# PCB-BI8-SE-C330.net
KiCad netlist of a schematic drawn in EAGLE
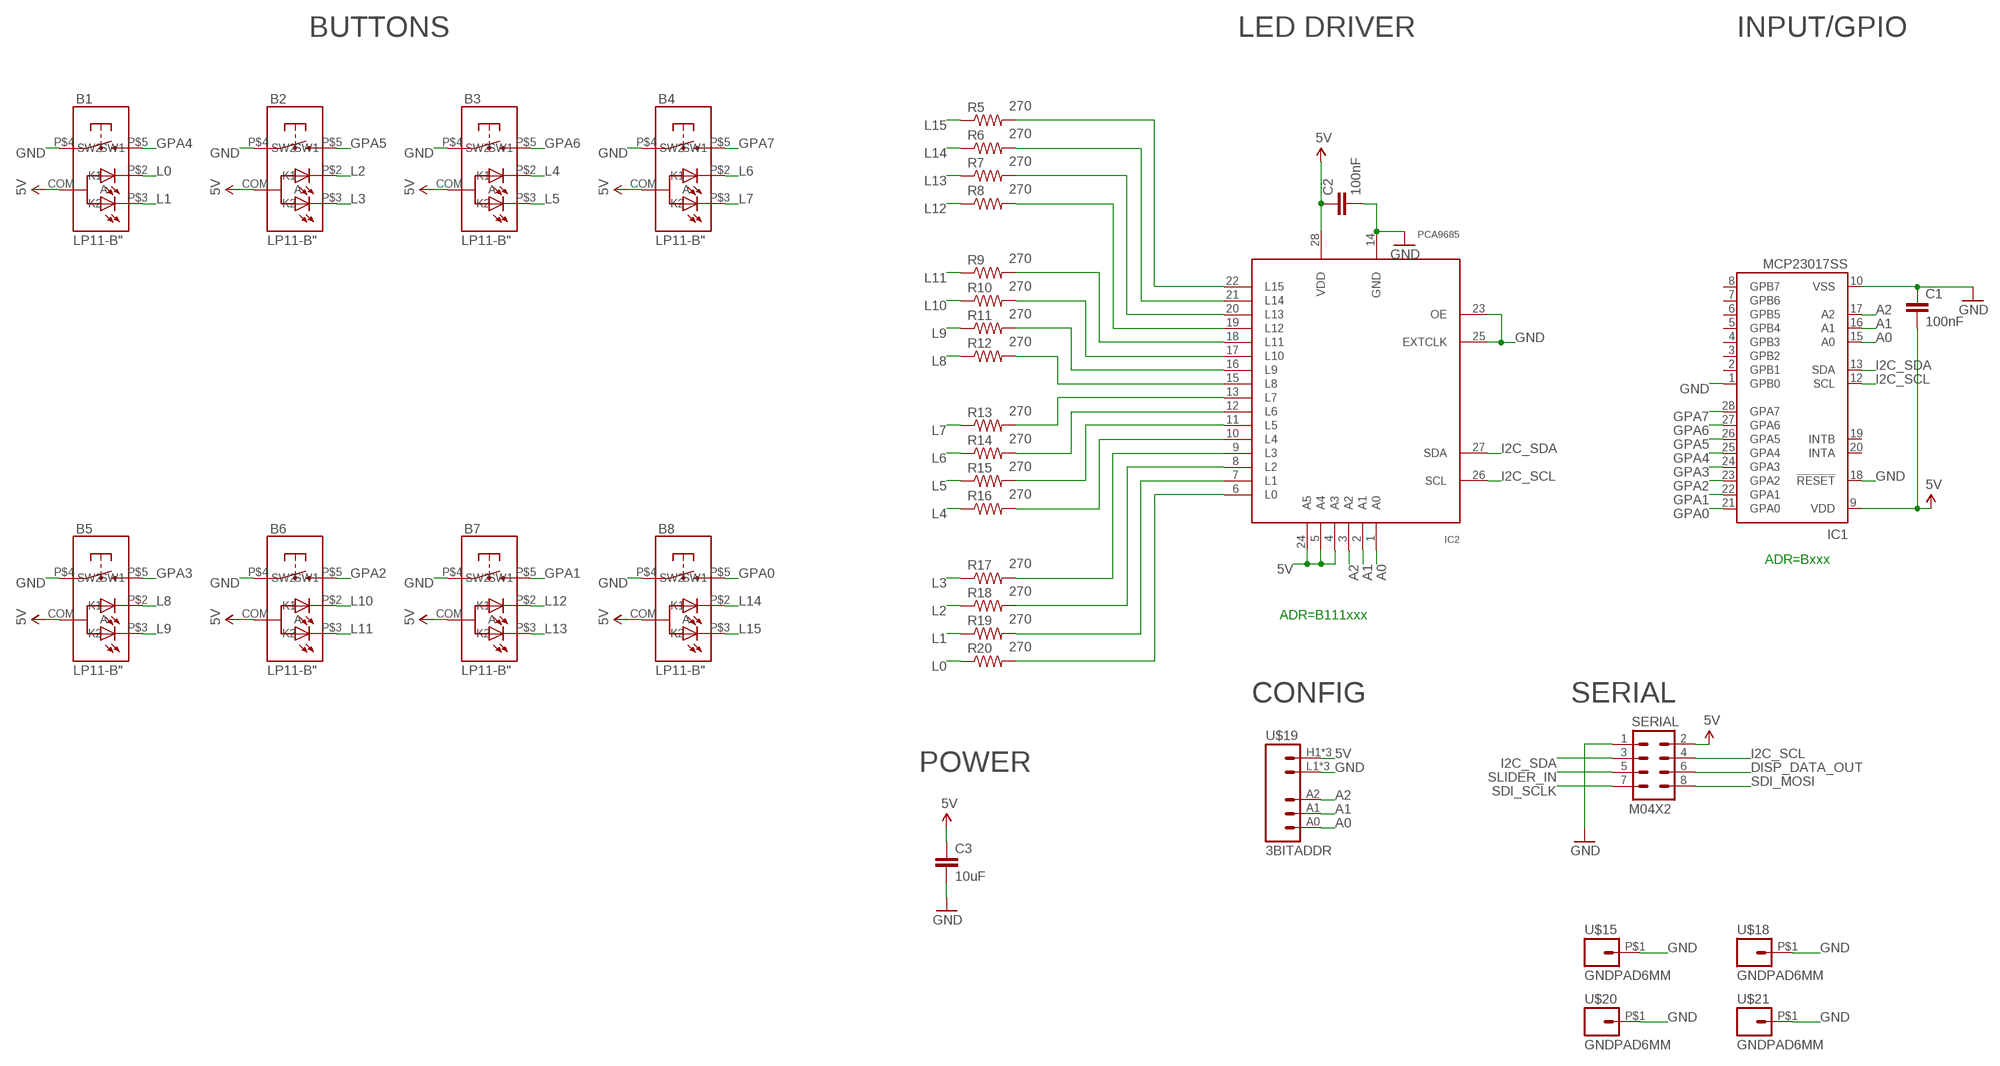
[diagram p0: schematic, sheet 1]

(export (version "E")
  (design (tool "Eeschema 10.0.6"))
  (components
    (comp (ref "B1")
      (value "LP11-B\"")
      (footprint "eagle-import:LP11")
      (libsource (lib "eagle-import") (part "LP11-B{dblquote}"))
    )
    (comp (ref "B2")
      (value "LP11-B\"")
      (footprint "eagle-import:LP11")
      (libsource (lib "eagle-import") (part "LP11-B{dblquote}"))
    )
    (comp (ref "B3")
      (value "LP11-B\"")
      (footprint "eagle-import:LP11")
      (libsource (lib "eagle-import") (part "LP11-B{dblquote}"))
    )
    (comp (ref "B4")
      (value "LP11-B\"")
      (footprint "eagle-import:LP11")
      (libsource (lib "eagle-import") (part "LP11-B{dblquote}"))
    )
    (comp (ref "B5")
      (value "LP11-B\"")
      (footprint "eagle-import:LP11")
      (libsource (lib "eagle-import") (part "LP11-B{dblquote}"))
    )
    (comp (ref "B6")
      (value "LP11-B\"")
      (footprint "eagle-import:LP11")
      (libsource (lib "eagle-import") (part "LP11-B{dblquote}"))
    )
    (comp (ref "B7")
      (value "LP11-B\"")
      (footprint "eagle-import:LP11")
      (libsource (lib "eagle-import") (part "LP11-B{dblquote}"))
    )
    (comp (ref "B8")
      (value "LP11-B\"")
      (footprint "eagle-import:LP11")
      (libsource (lib "eagle-import") (part "LP11-B{dblquote}"))
    )
    (comp (ref "C1")
      (value "100nF")
      (footprint "eagle-import:0603-CAP")
      (libsource (lib "eagle-import") (part "CAP0603-CAP"))
    )
    (comp (ref "C2")
      (value "100nF")
      (footprint "eagle-import:0603-CAP")
      (libsource (lib "eagle-import") (part "CAP0603-CAP"))
    )
    (comp (ref "C3")
      (value "10uF")
      (footprint "eagle-import:0805")
      (libsource (lib "eagle-import") (part "CAP0805"))
    )
    (comp (ref "IC1")
      (value "MCP23017SS")
      (footprint "eagle-import:SSOP28")
      (fields
        (field (name "MF") "MICROCHIP")
        (field (name "MPN") "MCP23017-E/SS")
        (field (name "MPN_1") "MCP23017-E/SS")
        (field (name "OC_FARNELL") "1467674")
        (field (name "OC_NEWARK") "31K2960")
      )
      (libsource (lib "eagle-import") (part "MCP23017SS"))
    )
    (comp (ref "IC2")
      (value "PCA9685")
      (footprint "eagle-import:TSSOP28")
      (libsource (lib "eagle-import") (part "PCA9685"))
    )
    (comp (ref "R5")
      (value "270")
      (footprint "eagle-import:0603-RES")
      (libsource (lib "eagle-import") (part "RESISTOR0603-RES"))
    )
    (comp (ref "R6")
      (value "270")
      (footprint "eagle-import:0603-RES")
      (libsource (lib "eagle-import") (part "RESISTOR0603-RES"))
    )
    (comp (ref "R7")
      (value "270")
      (footprint "eagle-import:0603-RES")
      (libsource (lib "eagle-import") (part "RESISTOR0603-RES"))
    )
    (comp (ref "R8")
      (value "270")
      (footprint "eagle-import:0603-RES")
      (libsource (lib "eagle-import") (part "RESISTOR0603-RES"))
    )
    (comp (ref "R9")
      (value "270")
      (footprint "eagle-import:0603-RES")
      (libsource (lib "eagle-import") (part "RESISTOR0603-RES"))
    )
    (comp (ref "R10")
      (value "270")
      (footprint "eagle-import:0603-RES")
      (libsource (lib "eagle-import") (part "RESISTOR0603-RES"))
    )
    (comp (ref "R11")
      (value "270")
      (footprint "eagle-import:0603-RES")
      (libsource (lib "eagle-import") (part "RESISTOR0603-RES"))
    )
    (comp (ref "R12")
      (value "270")
      (footprint "eagle-import:0603-RES")
      (libsource (lib "eagle-import") (part "RESISTOR0603-RES"))
    )
    (comp (ref "R13")
      (value "270")
      (footprint "eagle-import:0603-RES")
      (libsource (lib "eagle-import") (part "RESISTOR0603-RES"))
    )
    (comp (ref "R14")
      (value "270")
      (footprint "eagle-import:0603-RES")
      (libsource (lib "eagle-import") (part "RESISTOR0603-RES"))
    )
    (comp (ref "R15")
      (value "270")
      (footprint "eagle-import:0603-RES")
      (libsource (lib "eagle-import") (part "RESISTOR0603-RES"))
    )
    (comp (ref "R16")
      (value "270")
      (footprint "eagle-import:0603-RES")
      (libsource (lib "eagle-import") (part "RESISTOR0603-RES"))
    )
    (comp (ref "R17")
      (value "270")
      (footprint "eagle-import:0603-RES")
      (libsource (lib "eagle-import") (part "RESISTOR0603-RES"))
    )
    (comp (ref "R18")
      (value "270")
      (footprint "eagle-import:0603-RES")
      (libsource (lib "eagle-import") (part "RESISTOR0603-RES"))
    )
    (comp (ref "R19")
      (value "270")
      (footprint "eagle-import:0603-RES")
      (libsource (lib "eagle-import") (part "RESISTOR0603-RES"))
    )
    (comp (ref "R20")
      (value "270")
      (footprint "eagle-import:0603-RES")
      (libsource (lib "eagle-import") (part "RESISTOR0603-RES"))
    )
    (comp (ref "SERIAL")
      (value "M04X2")
      (footprint "eagle-import:2X4")
      (libsource (lib "eagle-import") (part "M04X2"))
    )
    (comp (ref "U$15")
      (value "GNDPAD6MM")
      (footprint "eagle-import:3.2MMPAD6MM")
      (libsource (lib "eagle-import") (part "GNDPAD6MM"))
    )
    (comp (ref "U$18")
      (value "GNDPAD6MM")
      (footprint "eagle-import:3.2MMPAD6MM")
      (libsource (lib "eagle-import") (part "GNDPAD6MM"))
    )
    (comp (ref "U$19")
      (value "3BITADDR")
      (footprint "eagle-import:3BITADDR")
      (libsource (lib "eagle-import") (part "3BITADDR"))
    )
    (comp (ref "U$20")
      (value "GNDPAD6MM")
      (footprint "eagle-import:3.2MMPAD6MM")
      (libsource (lib "eagle-import") (part "GNDPAD6MM"))
    )
    (comp (ref "U$21")
      (value "GNDPAD6MM")
      (footprint "eagle-import:3.2MMPAD6MM")
      (libsource (lib "eagle-import") (part "GNDPAD6MM"))
    )
  )
  (nets
    (net (code "1") (name "/A0") (class "Default")
      (node (ref "IC1") (pin "15") (pinfunction "A0_15") (pintype "input"))
      (node (ref "IC2") (pin "1") (pinfunction "A0_1") (pintype "input"))
      (node (ref "U$19") (pin "A0") (pinfunction "A0_A0") (pintype "passive"))
    )
    (net (code "2") (name "/A1") (class "Default")
      (node (ref "IC1") (pin "16") (pinfunction "A1_16") (pintype "input"))
      (node (ref "IC2") (pin "2") (pinfunction "A1_2") (pintype "input"))
      (node (ref "U$19") (pin "A1") (pinfunction "A1_A1") (pintype "passive"))
    )
    (net (code "3") (name "/A2") (class "Default")
      (node (ref "IC1") (pin "17") (pinfunction "A2_17") (pintype "input"))
      (node (ref "IC2") (pin "3") (pinfunction "A2_3") (pintype "input"))
      (node (ref "U$19") (pin "A2") (pinfunction "A2_A2") (pintype "passive"))
    )
    (net (code "4") (name "/DISP_DATA_OUT") (class "Default")
      (node (ref "SERIAL") (pin "6") (pinfunction "6_6") (pintype "passive"))
    )
    (net (code "5") (name "/GPA0") (class "Default")
      (node (ref "B8") (pin "P$5") (pinfunction "SW2_P$5") (pintype "bidirectional"))
      (node (ref "IC1") (pin "21") (pinfunction "GPA0_21") (pintype "bidirectional"))
    )
    (net (code "6") (name "/GPA1") (class "Default")
      (node (ref "B7") (pin "P$5") (pinfunction "SW2_P$5") (pintype "bidirectional"))
      (node (ref "IC1") (pin "22") (pinfunction "GPA1_22") (pintype "bidirectional"))
    )
    (net (code "7") (name "/GPA2") (class "Default")
      (node (ref "B6") (pin "P$5") (pinfunction "SW2_P$5") (pintype "bidirectional"))
      (node (ref "IC1") (pin "23") (pinfunction "GPA2_23") (pintype "bidirectional"))
    )
    (net (code "8") (name "/GPA3") (class "Default")
      (node (ref "B5") (pin "P$5") (pinfunction "SW2_P$5") (pintype "bidirectional"))
      (node (ref "IC1") (pin "24") (pinfunction "GPA3_24") (pintype "bidirectional"))
    )
    (net (code "9") (name "/GPA4") (class "Default")
      (node (ref "B1") (pin "P$5") (pinfunction "SW2_P$5") (pintype "bidirectional"))
      (node (ref "IC1") (pin "25") (pinfunction "GPA4_25") (pintype "bidirectional"))
    )
    (net (code "10") (name "/GPA5") (class "Default")
      (node (ref "B2") (pin "P$5") (pinfunction "SW2_P$5") (pintype "bidirectional"))
      (node (ref "IC1") (pin "26") (pinfunction "GPA5_26") (pintype "bidirectional"))
    )
    (net (code "11") (name "/GPA6") (class "Default")
      (node (ref "B3") (pin "P$5") (pinfunction "SW2_P$5") (pintype "bidirectional"))
      (node (ref "IC1") (pin "27") (pinfunction "GPA6_27") (pintype "bidirectional"))
    )
    (net (code "12") (name "/GPA7") (class "Default")
      (node (ref "B4") (pin "P$5") (pinfunction "SW2_P$5") (pintype "bidirectional"))
      (node (ref "IC1") (pin "28") (pinfunction "GPA7_28") (pintype "bidirectional"))
    )
    (net (code "13") (name "/I2C_SCL") (class "Default")
      (node (ref "IC1") (pin "12") (pinfunction "SCL_12") (pintype "input"))
      (node (ref "IC2") (pin "26") (pinfunction "SCL_26") (pintype "input"))
      (node (ref "SERIAL") (pin "4") (pinfunction "4_4") (pintype "passive"))
    )
    (net (code "14") (name "/I2C_SDA") (class "Default")
      (node (ref "IC1") (pin "13") (pinfunction "SDA_13") (pintype "bidirectional"))
      (node (ref "IC2") (pin "27") (pinfunction "SDA_27") (pintype "input"))
      (node (ref "SERIAL") (pin "3") (pinfunction "3_3") (pintype "passive"))
    )
    (net (code "15") (name "/L0") (class "Default")
      (node (ref "B1") (pin "P$2") (pinfunction "K1_P$2") (pintype "bidirectional"))
      (node (ref "R20") (pin "1") (pinfunction "1_1") (pintype "passive"))
    )
    (net (code "16") (name "/L1") (class "Default")
      (node (ref "B1") (pin "P$3") (pinfunction "K2_P$3") (pintype "bidirectional"))
      (node (ref "R19") (pin "1") (pinfunction "1_1") (pintype "passive"))
    )
    (net (code "17") (name "/L2") (class "Default")
      (node (ref "B2") (pin "P$2") (pinfunction "K1_P$2") (pintype "bidirectional"))
      (node (ref "R18") (pin "1") (pinfunction "1_1") (pintype "passive"))
    )
    (net (code "18") (name "/L3") (class "Default")
      (node (ref "B2") (pin "P$3") (pinfunction "K2_P$3") (pintype "bidirectional"))
      (node (ref "R17") (pin "1") (pinfunction "1_1") (pintype "passive"))
    )
    (net (code "19") (name "/L4") (class "Default")
      (node (ref "B3") (pin "P$2") (pinfunction "K1_P$2") (pintype "bidirectional"))
      (node (ref "R16") (pin "1") (pinfunction "1_1") (pintype "passive"))
    )
    (net (code "20") (name "/L5") (class "Default")
      (node (ref "B3") (pin "P$3") (pinfunction "K2_P$3") (pintype "bidirectional"))
      (node (ref "R15") (pin "1") (pinfunction "1_1") (pintype "passive"))
    )
    (net (code "21") (name "/L6") (class "Default")
      (node (ref "B4") (pin "P$2") (pinfunction "K1_P$2") (pintype "bidirectional"))
      (node (ref "R14") (pin "1") (pinfunction "1_1") (pintype "passive"))
    )
    (net (code "22") (name "/L7") (class "Default")
      (node (ref "B4") (pin "P$3") (pinfunction "K2_P$3") (pintype "bidirectional"))
      (node (ref "R13") (pin "1") (pinfunction "1_1") (pintype "passive"))
    )
    (net (code "23") (name "/L8") (class "Default")
      (node (ref "B5") (pin "P$2") (pinfunction "K1_P$2") (pintype "bidirectional"))
      (node (ref "R12") (pin "1") (pinfunction "1_1") (pintype "passive"))
    )
    (net (code "24") (name "/L9") (class "Default")
      (node (ref "B5") (pin "P$3") (pinfunction "K2_P$3") (pintype "bidirectional"))
      (node (ref "R11") (pin "1") (pinfunction "1_1") (pintype "passive"))
    )
    (net (code "25") (name "/L10") (class "Default")
      (node (ref "B6") (pin "P$2") (pinfunction "K1_P$2") (pintype "bidirectional"))
      (node (ref "R10") (pin "1") (pinfunction "1_1") (pintype "passive"))
    )
    (net (code "26") (name "/L11") (class "Default")
      (node (ref "B6") (pin "P$3") (pinfunction "K2_P$3") (pintype "bidirectional"))
      (node (ref "R9") (pin "1") (pinfunction "1_1") (pintype "passive"))
    )
    (net (code "27") (name "/L12") (class "Default")
      (node (ref "B7") (pin "P$2") (pinfunction "K1_P$2") (pintype "bidirectional"))
      (node (ref "R8") (pin "1") (pinfunction "1_1") (pintype "passive"))
    )
    (net (code "28") (name "/L13") (class "Default")
      (node (ref "B7") (pin "P$3") (pinfunction "K2_P$3") (pintype "bidirectional"))
      (node (ref "R7") (pin "1") (pinfunction "1_1") (pintype "passive"))
    )
    (net (code "29") (name "/L14") (class "Default")
      (node (ref "B8") (pin "P$2") (pinfunction "K1_P$2") (pintype "bidirectional"))
      (node (ref "R6") (pin "1") (pinfunction "1_1") (pintype "passive"))
    )
    (net (code "30") (name "/L15") (class "Default")
      (node (ref "B8") (pin "P$3") (pinfunction "K2_P$3") (pintype "bidirectional"))
      (node (ref "R5") (pin "1") (pinfunction "1_1") (pintype "passive"))
    )
    (net (code "31") (name "/SDI_MOSI") (class "Default")
      (node (ref "SERIAL") (pin "8") (pinfunction "8_8") (pintype "passive"))
    )
    (net (code "32") (name "/SDI_SCLK") (class "Default")
      (node (ref "SERIAL") (pin "7") (pinfunction "7_7") (pintype "passive"))
    )
    (net (code "33") (name "/SLIDER_IN") (class "Default")
      (node (ref "SERIAL") (pin "5") (pinfunction "5_5") (pintype "passive"))
    )
    (net (code "34") (name "5V") (class "Default")
      (node (ref "B1") (pin "COM") (pinfunction "A_COM") (pintype "bidirectional"))
      (node (ref "B2") (pin "COM") (pinfunction "A_COM") (pintype "bidirectional"))
      (node (ref "B3") (pin "COM") (pinfunction "A_COM") (pintype "bidirectional"))
      (node (ref "B4") (pin "COM") (pinfunction "A_COM") (pintype "bidirectional"))
      (node (ref "B5") (pin "COM") (pinfunction "A_COM") (pintype "bidirectional"))
      (node (ref "B6") (pin "COM") (pinfunction "A_COM") (pintype "bidirectional"))
      (node (ref "B7") (pin "COM") (pinfunction "A_COM") (pintype "bidirectional"))
      (node (ref "B8") (pin "COM") (pinfunction "A_COM") (pintype "bidirectional"))
      (node (ref "C1") (pin "2") (pinfunction "2_2") (pintype "passive"))
      (node (ref "C2") (pin "1") (pinfunction "1_1") (pintype "passive"))
      (node (ref "C3") (pin "1") (pinfunction "1_1") (pintype "passive"))
      (node (ref "IC1") (pin "9") (pinfunction "VDD_9") (pintype "power_in"))
      (node (ref "IC2") (pin "24") (pinfunction "A5_24") (pintype "input"))
      (node (ref "IC2") (pin "28") (pinfunction "VDD_28") (pintype "power_in"))
      (node (ref "IC2") (pin "4") (pinfunction "A3_4") (pintype "input"))
      (node (ref "IC2") (pin "5") (pinfunction "A4_5") (pintype "input"))
      (node (ref "SERIAL") (pin "2") (pinfunction "2_2") (pintype "passive"))
      (node (ref "U$19") (pin "H1") (pinfunction "VCC_H1") (pintype "passive"))
      (node (ref "U$19") (pin "H2") (pinfunction "VCC_H2") (pintype "passive"))
      (node (ref "U$19") (pin "H3") (pinfunction "VCC_H3") (pintype "passive"))
    )
    (net (code "35") (name "GND") (class "Default")
      (node (ref "B1") (pin "P$4") (pinfunction "SW1_P$4") (pintype "bidirectional"))
      (node (ref "B2") (pin "P$4") (pinfunction "SW1_P$4") (pintype "bidirectional"))
      (node (ref "B3") (pin "P$4") (pinfunction "SW1_P$4") (pintype "bidirectional"))
      (node (ref "B4") (pin "P$4") (pinfunction "SW1_P$4") (pintype "bidirectional"))
      (node (ref "B5") (pin "P$4") (pinfunction "SW1_P$4") (pintype "bidirectional"))
      (node (ref "B6") (pin "P$4") (pinfunction "SW1_P$4") (pintype "bidirectional"))
      (node (ref "B7") (pin "P$4") (pinfunction "SW1_P$4") (pintype "bidirectional"))
      (node (ref "B8") (pin "P$4") (pinfunction "SW1_P$4") (pintype "bidirectional"))
      (node (ref "C1") (pin "1") (pinfunction "1_1") (pintype "passive"))
      (node (ref "C2") (pin "2") (pinfunction "2_2") (pintype "passive"))
      (node (ref "C3") (pin "2") (pinfunction "2_2") (pintype "passive"))
      (node (ref "IC1") (pin "1") (pinfunction "GPB0_1") (pintype "bidirectional"))
      (node (ref "IC1") (pin "10") (pinfunction "VSS_10") (pintype "power_in"))
      (node (ref "IC1") (pin "18") (pinfunction "~{RESET}_18") (pintype "input"))
      (node (ref "IC2") (pin "14") (pinfunction "GND_14") (pintype "power_in"))
      (node (ref "IC2") (pin "23") (pinfunction "OE_23") (pintype "input"))
      (node (ref "IC2") (pin "25") (pinfunction "EXTCLK_25") (pintype "input"))
      (node (ref "SERIAL") (pin "1") (pinfunction "1_1") (pintype "passive"))
      (node (ref "U$15") (pin "P$1") (pinfunction "1_P$1") (pintype "passive"))
      (node (ref "U$18") (pin "P$1") (pinfunction "1_P$1") (pintype "passive"))
      (node (ref "U$19") (pin "L1") (pinfunction "GND_L1") (pintype "passive"))
      (node (ref "U$19") (pin "L2") (pinfunction "GND_L2") (pintype "passive"))
      (node (ref "U$19") (pin "L3") (pinfunction "GND_L3") (pintype "passive"))
      (node (ref "U$20") (pin "P$1") (pinfunction "1_P$1") (pintype "passive"))
      (node (ref "U$21") (pin "P$1") (pinfunction "1_P$1") (pintype "passive"))
    )
    (net (code "36") (name "Net-(IC2-L0)") (class "Default")
      (node (ref "IC2") (pin "6") (pinfunction "L0_6") (pintype "output"))
      (node (ref "R20") (pin "2") (pinfunction "2_2") (pintype "passive"))
    )
    (net (code "37") (name "Net-(IC2-L1)") (class "Default")
      (node (ref "IC2") (pin "7") (pinfunction "L1_7") (pintype "output"))
      (node (ref "R19") (pin "2") (pinfunction "2_2") (pintype "passive"))
    )
    (net (code "38") (name "Net-(IC2-L2)") (class "Default")
      (node (ref "IC2") (pin "8") (pinfunction "L2_8") (pintype "output"))
      (node (ref "R18") (pin "2") (pinfunction "2_2") (pintype "passive"))
    )
    (net (code "39") (name "Net-(IC2-L3)") (class "Default")
      (node (ref "IC2") (pin "9") (pinfunction "L3_9") (pintype "output"))
      (node (ref "R17") (pin "2") (pinfunction "2_2") (pintype "passive"))
    )
    (net (code "40") (name "Net-(IC2-L4)") (class "Default")
      (node (ref "IC2") (pin "10") (pinfunction "L4_10") (pintype "output"))
      (node (ref "R16") (pin "2") (pinfunction "2_2") (pintype "passive"))
    )
    (net (code "41") (name "Net-(IC2-L5)") (class "Default")
      (node (ref "IC2") (pin "11") (pinfunction "L5_11") (pintype "output"))
      (node (ref "R15") (pin "2") (pinfunction "2_2") (pintype "passive"))
    )
    (net (code "42") (name "Net-(IC2-L6)") (class "Default")
      (node (ref "IC2") (pin "12") (pinfunction "L6_12") (pintype "output"))
      (node (ref "R14") (pin "2") (pinfunction "2_2") (pintype "passive"))
    )
    (net (code "43") (name "Net-(IC2-L7)") (class "Default")
      (node (ref "IC2") (pin "13") (pinfunction "L7_13") (pintype "output"))
      (node (ref "R13") (pin "2") (pinfunction "2_2") (pintype "passive"))
    )
    (net (code "44") (name "Net-(IC2-L8)") (class "Default")
      (node (ref "IC2") (pin "15") (pinfunction "L8_15") (pintype "output"))
      (node (ref "R12") (pin "2") (pinfunction "2_2") (pintype "passive"))
    )
    (net (code "45") (name "Net-(IC2-L9)") (class "Default")
      (node (ref "IC2") (pin "16") (pinfunction "L9_16") (pintype "output"))
      (node (ref "R11") (pin "2") (pinfunction "2_2") (pintype "passive"))
    )
    (net (code "46") (name "Net-(IC2-L10)") (class "Default")
      (node (ref "IC2") (pin "17") (pinfunction "L10_17") (pintype "output"))
      (node (ref "R10") (pin "2") (pinfunction "2_2") (pintype "passive"))
    )
    (net (code "47") (name "Net-(IC2-L11)") (class "Default")
      (node (ref "IC2") (pin "18") (pinfunction "L11_18") (pintype "output"))
      (node (ref "R9") (pin "2") (pinfunction "2_2") (pintype "passive"))
    )
    (net (code "48") (name "Net-(IC2-L12)") (class "Default")
      (node (ref "IC2") (pin "19") (pinfunction "L12_19") (pintype "output"))
      (node (ref "R8") (pin "2") (pinfunction "2_2") (pintype "passive"))
    )
    (net (code "49") (name "Net-(IC2-L13)") (class "Default")
      (node (ref "IC2") (pin "20") (pinfunction "L13_20") (pintype "output"))
      (node (ref "R7") (pin "2") (pinfunction "2_2") (pintype "passive"))
    )
    (net (code "50") (name "Net-(IC2-L14)") (class "Default")
      (node (ref "IC2") (pin "21") (pinfunction "L14_21") (pintype "output"))
      (node (ref "R6") (pin "2") (pinfunction "2_2") (pintype "passive"))
    )
    (net (code "51") (name "Net-(IC2-L15)") (class "Default")
      (node (ref "IC2") (pin "22") (pinfunction "L15_22") (pintype "output"))
      (node (ref "R5") (pin "2") (pinfunction "2_2") (pintype "passive"))
    )
    (net (code "52") (name "unconnected-(IC1-GPB1-Pad2)") (class "Default")
      (node (ref "IC1") (pin "2") (pinfunction "GPB1_2") (pintype "bidirectional"))
    )
    (net (code "53") (name "unconnected-(IC1-GPB2-Pad3)") (class "Default")
      (node (ref "IC1") (pin "3") (pinfunction "GPB2_3") (pintype "bidirectional"))
    )
    (net (code "54") (name "unconnected-(IC1-GPB3-Pad4)") (class "Default")
      (node (ref "IC1") (pin "4") (pinfunction "GPB3_4") (pintype "bidirectional"))
    )
    (net (code "55") (name "unconnected-(IC1-GPB4-Pad5)") (class "Default")
      (node (ref "IC1") (pin "5") (pinfunction "GPB4_5") (pintype "bidirectional"))
    )
    (net (code "56") (name "unconnected-(IC1-GPB5-Pad6)") (class "Default")
      (node (ref "IC1") (pin "6") (pinfunction "GPB5_6") (pintype "bidirectional"))
    )
    (net (code "57") (name "unconnected-(IC1-GPB6-Pad7)") (class "Default")
      (node (ref "IC1") (pin "7") (pinfunction "GPB6_7") (pintype "bidirectional"))
    )
    (net (code "58") (name "unconnected-(IC1-GPB7-Pad8)") (class "Default")
      (node (ref "IC1") (pin "8") (pinfunction "GPB7_8") (pintype "bidirectional"))
    )
    (net (code "59") (name "unconnected-(IC1-INTA-Pad20)") (class "Default")
      (node (ref "IC1") (pin "20") (pinfunction "INTA_20") (pintype "output"))
    )
    (net (code "60") (name "unconnected-(IC1-INTB-Pad19)") (class "Default")
      (node (ref "IC1") (pin "19") (pinfunction "INTB_19") (pintype "output"))
    )
  )
)
